# cc2652r.net
KiCad netlist of a schematic drawn in EAGLE
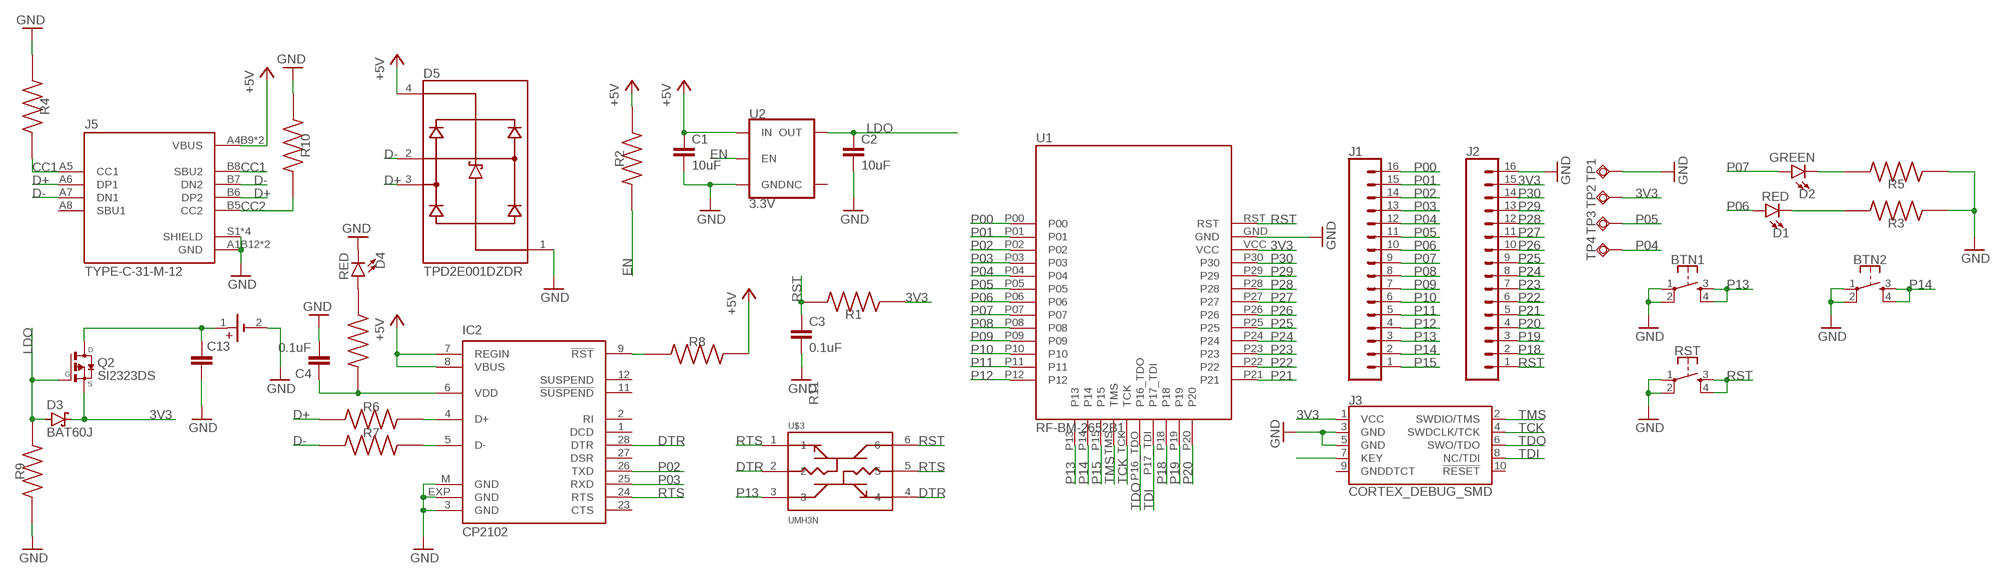
[diagram p0: schematic, sheet 1]

(export (version "E")
  (design (tool "Eeschema 10.0.6"))
  (components
    (comp (ref "BT2")
      (value "79527141")
      (footprint "eagle-import:79527141")
      (fields
        (field (name "DIGIKEY_PART_NO") "732-12325-2-ND")
        (field (name "MANUFACTURER") "Wurth Electronics Inc.")
        (field (name "CREATED_BY") "PCBLayout.com")
      )
      (libsource (lib "eagle-import") (part "79527141"))
    )
    (comp (ref "BTN1")
      (value "MOMENTARY-SWITCH-SPST-2-SMD-4.6X2.8MM")
      (footprint "eagle-import:TACTILE_SWITCH_SMD_4.6X2.8MM")
      (libsource (lib "eagle-import") (part "MOMENTARY-SWITCH-SPST-2-SMD-4.6X2.8MM"))
    )
    (comp (ref "BTN2")
      (value "MOMENTARY-SWITCH-SPST-2-SMD-4.6X2.8MM")
      (footprint "eagle-import:TACTILE_SWITCH_SMD_4.6X2.8MM")
      (libsource (lib "eagle-import") (part "MOMENTARY-SWITCH-SPST-2-SMD-4.6X2.8MM"))
    )
    (comp (ref "C1")
      (value "10uF")
      (footprint "eagle-import:0603")
      (libsource (lib "eagle-import") (part "10UF-0603-6.3V-20%"))
    )
    (comp (ref "C2")
      (value "10uF")
      (footprint "eagle-import:0603")
      (libsource (lib "eagle-import") (part "10UF-0603-6.3V-20%"))
    )
    (comp (ref "C3")
      (value "0.1uF")
      (footprint "eagle-import:0603")
      (libsource (lib "eagle-import") (part "0.1UF-0603-25V-(+80/-20%)"))
    )
    (comp (ref "C4")
      (value "0.1uF")
      (footprint "eagle-import:0603")
      (libsource (lib "eagle-import") (part "0.1UF-0603-25V-(+80/-20%)"))
    )
    (comp (ref "C13")
      (value "C_TANTALUM-2917(7343-METRIC)")
      (footprint "eagle-import:CAPM7343X310")
      (libsource (lib "eagle-import") (part "CTANTALUM-2917(7343-METRIC)_"))
    )
    (comp (ref "D1")
      (value "RED")
      (footprint "eagle-import:LED-0603")
      (libsource (lib "eagle-import") (part "LED-RED0603"))
    )
    (comp (ref "D2")
      (value "GREEN")
      (footprint "eagle-import:LED-0603")
      (libsource (lib "eagle-import") (part "LED-GREEN0603"))
    )
    (comp (ref "D3")
      (value "BAT60J")
      (footprint "eagle-import:SOD323_ST")
      (libsource (lib "eagle-import") (part "BAT60J"))
    )
    (comp (ref "D4")
      (value "RED")
      (footprint "eagle-import:LED-0603")
      (libsource (lib "eagle-import") (part "LED-RED0603"))
    )
    (comp (ref "D5")
      (value "TPD2E001DZDR")
      (footprint "eagle-import:SOT192P237X122-4N")
      (fields (field (name "MF") "Texas Instruments"))
      (libsource (lib "eagle-import") (part "TPD2E001DZDR"))
    )
    (comp (ref "IC2")
      (value "CP2102")
      (footprint "eagle-import:MLP28")
      (fields (field (name "MF") "FARNELL") (field (name "MPN") "CP2102-GM"))
      (libsource (lib "eagle-import") (part "CP2102"))
    )
    (comp (ref "J1")
      (value "CONN_161X16_NO_SILK")
      (footprint "eagle-import:1X16_NO_SILK")
      (libsource (lib "eagle-import") (part "CONN_161X16_NO_SILK"))
    )
    (comp (ref "J2")
      (value "CONN_161X16_NO_SILK")
      (footprint "eagle-import:1X16_NO_SILK")
      (libsource (lib "eagle-import") (part "CONN_161X16_NO_SILK"))
    )
    (comp (ref "J3")
      (value "CORTEX_DEBUG_SMD")
      (footprint "eagle-import:SAMTECH_FTSH-105-01")
      (libsource (lib "eagle-import") (part "CORTEX_DEBUG_SMD"))
    )
    (comp (ref "J5")
      (value "TYPE-C-31-M-12")
      (footprint "eagle-import:HRO_TYPE-C-31-M-12")
      (fields (field (name "MF") "HRO Electronics Co., Ltd."))
      (libsource (lib "eagle-import") (part "TYPE-C-31-M-12"))
    )
    (comp (ref "Q2")
      (value "SI2323DS")
      (footprint "eagle-import:SOT23")
      (fields (field (name "MF") "Vishay Siliconix"))
      (libsource (lib "eagle-import") (part "SI2323DS"))
    )
    (comp (ref "R1")
      (value "RC0402FR-073M6L")
      (footprint "eagle-import:RESC1005X40N")
      (fields (field (name "MF") "Yageo"))
      (libsource (lib "eagle-import") (part "RC0402FR-073M6L"))
    )
    (comp (ref "R2")
      (value "RC0402FR-073M6L")
      (footprint "eagle-import:RESC1005X40N")
      (fields (field (name "MF") "Yageo"))
      (libsource (lib "eagle-import") (part "RC0402FR-073M6L"))
    )
    (comp (ref "R3")
      (value "RC0402FR-073M6L")
      (footprint "eagle-import:RESC1005X40N")
      (fields (field (name "MF") "Yageo"))
      (libsource (lib "eagle-import") (part "RC0402FR-073M6L"))
    )
    (comp (ref "R4")
      (value "RC0402FR-073M6L")
      (footprint "eagle-import:RESC1005X40N")
      (fields (field (name "MF") "Yageo"))
      (libsource (lib "eagle-import") (part "RC0402FR-073M6L"))
    )
    (comp (ref "R5")
      (value "RC0402FR-073M6L")
      (footprint "eagle-import:RESC1005X40N")
      (fields (field (name "MF") "Yageo"))
      (libsource (lib "eagle-import") (part "RC0402FR-073M6L"))
    )
    (comp (ref "R6")
      (value "RC0402FR-073M6L")
      (footprint "eagle-import:RESC1005X40N")
      (fields (field (name "MF") "Yageo"))
      (libsource (lib "eagle-import") (part "RC0402FR-073M6L"))
    )
    (comp (ref "R7")
      (value "RC0402FR-073M6L")
      (footprint "eagle-import:RESC1005X40N")
      (fields (field (name "MF") "Yageo"))
      (libsource (lib "eagle-import") (part "RC0402FR-073M6L"))
    )
    (comp (ref "R8")
      (value "RC0402FR-073M6L")
      (footprint "eagle-import:RESC1005X40N")
      (fields (field (name "MF") "Yageo"))
      (libsource (lib "eagle-import") (part "RC0402FR-073M6L"))
    )
    (comp (ref "R9")
      (value "RC0402FR-073M6L")
      (footprint "eagle-import:RESC1005X40N")
      (fields (field (name "MF") "Yageo"))
      (libsource (lib "eagle-import") (part "RC0402FR-073M6L"))
    )
    (comp (ref "R10")
      (value "RC0402FR-073M6L")
      (footprint "eagle-import:RESC1005X40N")
      (fields (field (name "MF") "Yageo"))
      (libsource (lib "eagle-import") (part "RC0402FR-073M6L"))
    )
    (comp (ref "R11")
      (value "RC0402FR-073M6L")
      (footprint "eagle-import:RESC1005X40N")
      (fields (field (name "MF") "Yageo"))
      (libsource (lib "eagle-import") (part "RC0402FR-073M6L"))
    )
    (comp (ref "RST")
      (value "MOMENTARY-SWITCH-SPST-2-SMD-4.6X2.8MM")
      (footprint "eagle-import:TACTILE_SWITCH_SMD_4.6X2.8MM")
      (libsource (lib "eagle-import") (part "MOMENTARY-SWITCH-SPST-2-SMD-4.6X2.8MM"))
    )
    (comp (ref "TP1")
      (value "TPSQTP14R")
      (footprint "eagle-import:TP14R")
      (libsource (lib "eagle-import") (part "TPSQTP14R"))
    )
    (comp (ref "TP2")
      (value "TPSQTP14R")
      (footprint "eagle-import:TP14R")
      (libsource (lib "eagle-import") (part "TPSQTP14R"))
    )
    (comp (ref "TP3")
      (value "TPSQTP14R")
      (footprint "eagle-import:TP14R")
      (libsource (lib "eagle-import") (part "TPSQTP14R"))
    )
    (comp (ref "TP4")
      (value "TPSQTP14R")
      (footprint "eagle-import:TP14R")
      (libsource (lib "eagle-import") (part "TPSQTP14R"))
    )
    (comp (ref "U$3")
      (value "UMH3N")
      (footprint "eagle-import:SOP65P210X100-6N")
      (fields (field (name "MF") "Rohm"))
      (libsource (lib "eagle-import") (part "UMH3N"))
    )
    (comp (ref "U1")
      (value "RF-BM-2652B1")
      (footprint "eagle-import:RF-BM-2652B1")
      (libsource (lib "eagle-import") (part "RF-BM-2652B1"))
    )
    (comp (ref "U2")
      (value "3.3V")
      (footprint "eagle-import:SOT23-5")
      (libsource (lib "eagle-import") (part "V_REG_AP2112K-3.3V"))
    )
  )
  (nets
    (net (code "1") (name "+5V") (class "Default")
      (node (ref "C1") (pin "1") (pinfunction "1_1") (pintype "passive"))
      (node (ref "D5") (pin "4") (pinfunction "VCC_4") (pintype "power_in"))
      (node (ref "IC2") (pin "7") (pinfunction "REGIN_7") (pintype "passive"))
      (node (ref "IC2") (pin "8") (pinfunction "VBUS_8") (pintype "input"))
      (node (ref "J5") (pin "A4B9") (pinfunction "VBUS_A4B9") (pintype "power_in"))
      (node (ref "J5") (pin "B4A9") (pinfunction "VBUS_B4A9") (pintype "power_in"))
      (node (ref "R2") (pin "2") (pinfunction "2_2") (pintype "passive"))
      (node (ref "R8") (pin "2") (pinfunction "2_2") (pintype "passive"))
      (node (ref "U2") (pin "1") (pinfunction "IN_1") (pintype "input"))
    )
    (net (code "2") (name "/3V3") (class "Default")
      (node (ref "D3") (pin "C") (pinfunction "C_C") (pintype "passive"))
      (node (ref "J2") (pin "15") (pinfunction "15_15") (pintype "passive"))
      (node (ref "J3") (pin "1") (pinfunction "VCC_1") (pintype "bidirectional"))
      (node (ref "Q2") (pin "2") (pinfunction "S_2") (pintype "passive"))
      (node (ref "R1") (pin "1") (pinfunction "1_1") (pintype "passive"))
      (node (ref "TP2") (pin "TP") (pinfunction "TP_TP") (pintype "input"))
      (node (ref "U1") (pin "VCC") (pinfunction "VCC_VCC") (pintype "bidirectional"))
    )
    (net (code "3") (name "/CC1") (class "Default")
      (node (ref "J5") (pin "A5") (pinfunction "CC1_A5") (pintype "bidirectional"))
      (node (ref "J5") (pin "B8") (pinfunction "SBU2_B8") (pintype "bidirectional"))
      (node (ref "R4") (pin "2") (pinfunction "2_2") (pintype "passive"))
    )
    (net (code "4") (name "/CC2") (class "Default")
      (node (ref "J5") (pin "B5") (pinfunction "CC2_B5") (pintype "bidirectional"))
      (node (ref "R10") (pin "2") (pinfunction "2_2") (pintype "passive"))
    )
    (net (code "5") (name "/D+") (class "Default")
      (node (ref "D5") (pin "3") (pinfunction "IO2_3") (pintype "bidirectional"))
      (node (ref "J5") (pin "A6") (pinfunction "DP1_A6") (pintype "bidirectional"))
      (node (ref "J5") (pin "B6") (pinfunction "DP2_B6") (pintype "bidirectional"))
      (node (ref "R6") (pin "1") (pinfunction "1_1") (pintype "passive"))
    )
    (net (code "6") (name "/D-") (class "Default")
      (node (ref "D5") (pin "2") (pinfunction "IO1_2") (pintype "bidirectional"))
      (node (ref "J5") (pin "A7") (pinfunction "DN1_A7") (pintype "bidirectional"))
      (node (ref "J5") (pin "B7") (pinfunction "DN2_B7") (pintype "bidirectional"))
      (node (ref "R7") (pin "1") (pinfunction "1_1") (pintype "passive"))
    )
    (net (code "7") (name "/DTR") (class "Default")
      (node (ref "IC2") (pin "28") (pinfunction "DTR_28") (pintype "output"))
      (node (ref "U$3") (pin "2") (pinfunction "2_2") (pintype "bidirectional"))
      (node (ref "U$3") (pin "4") (pinfunction "4_4") (pintype "bidirectional"))
    )
    (net (code "8") (name "/EN") (class "Default")
      (node (ref "R2") (pin "1") (pinfunction "1_1") (pintype "passive"))
      (node (ref "U2") (pin "3") (pinfunction "EN_3") (pintype "input"))
    )
    (net (code "9") (name "/LDO") (class "Default")
      (node (ref "C2") (pin "1") (pinfunction "1_1") (pintype "passive"))
      (node (ref "D3") (pin "A") (pinfunction "A_A") (pintype "passive"))
      (node (ref "Q2") (pin "1") (pinfunction "G_1") (pintype "passive"))
      (node (ref "R9") (pin "2") (pinfunction "2_2") (pintype "passive"))
      (node (ref "U2") (pin "5") (pinfunction "OUT_5") (pintype "passive"))
    )
    (net (code "10") (name "/P00") (class "Default")
      (node (ref "J1") (pin "16") (pinfunction "16_16") (pintype "passive"))
      (node (ref "U1") (pin "P00") (pinfunction "P00_P00") (pintype "bidirectional"))
    )
    (net (code "11") (name "/P01") (class "Default")
      (node (ref "J1") (pin "15") (pinfunction "15_15") (pintype "passive"))
      (node (ref "U1") (pin "P01") (pinfunction "P01_P01") (pintype "bidirectional"))
    )
    (net (code "12") (name "/P02") (class "Default")
      (node (ref "IC2") (pin "26") (pinfunction "TXD_26") (pintype "output"))
      (node (ref "J1") (pin "14") (pinfunction "14_14") (pintype "passive"))
      (node (ref "U1") (pin "P02") (pinfunction "P02_P02") (pintype "bidirectional"))
    )
    (net (code "13") (name "/P03") (class "Default")
      (node (ref "IC2") (pin "25") (pinfunction "RXD_25") (pintype "input"))
      (node (ref "J1") (pin "13") (pinfunction "13_13") (pintype "passive"))
      (node (ref "U1") (pin "P03") (pinfunction "P03_P03") (pintype "bidirectional"))
    )
    (net (code "14") (name "/P04") (class "Default")
      (node (ref "J1") (pin "12") (pinfunction "12_12") (pintype "passive"))
      (node (ref "TP4") (pin "TP") (pinfunction "TP_TP") (pintype "input"))
      (node (ref "U1") (pin "P04") (pinfunction "P04_P04") (pintype "bidirectional"))
    )
    (net (code "15") (name "/P05") (class "Default")
      (node (ref "J1") (pin "11") (pinfunction "11_11") (pintype "passive"))
      (node (ref "TP3") (pin "TP") (pinfunction "TP_TP") (pintype "input"))
      (node (ref "U1") (pin "P05") (pinfunction "P05_P05") (pintype "bidirectional"))
    )
    (net (code "16") (name "/P06") (class "Default")
      (node (ref "D1") (pin "A") (pinfunction "A_A") (pintype "passive"))
      (node (ref "J1") (pin "10") (pinfunction "10_10") (pintype "passive"))
      (node (ref "U1") (pin "P06") (pinfunction "P06_P06") (pintype "bidirectional"))
    )
    (net (code "17") (name "/P07") (class "Default")
      (node (ref "D2") (pin "A") (pinfunction "A_A") (pintype "passive"))
      (node (ref "J1") (pin "9") (pinfunction "9_9") (pintype "passive"))
      (node (ref "U1") (pin "P07") (pinfunction "P07_P07") (pintype "bidirectional"))
    )
    (net (code "18") (name "/P08") (class "Default")
      (node (ref "J1") (pin "8") (pinfunction "8_8") (pintype "passive"))
      (node (ref "U1") (pin "P08") (pinfunction "P08_P08") (pintype "bidirectional"))
    )
    (net (code "19") (name "/P09") (class "Default")
      (node (ref "J1") (pin "7") (pinfunction "7_7") (pintype "passive"))
      (node (ref "U1") (pin "P09") (pinfunction "P09_P09") (pintype "bidirectional"))
    )
    (net (code "20") (name "/P10") (class "Default")
      (node (ref "J1") (pin "6") (pinfunction "6_6") (pintype "passive"))
      (node (ref "U1") (pin "P10") (pinfunction "P10_P10") (pintype "bidirectional"))
    )
    (net (code "21") (name "/P11") (class "Default")
      (node (ref "J1") (pin "5") (pinfunction "5_5") (pintype "passive"))
      (node (ref "U1") (pin "P11") (pinfunction "P11_P11") (pintype "bidirectional"))
    )
    (net (code "22") (name "/P12") (class "Default")
      (node (ref "J1") (pin "4") (pinfunction "4_4") (pintype "passive"))
      (node (ref "U1") (pin "P12") (pinfunction "P12_P12") (pintype "bidirectional"))
    )
    (net (code "23") (name "/P13") (class "Default")
      (node (ref "BTN1") (pin "3") (pinfunction "3_3") (pintype "passive"))
      (node (ref "BTN1") (pin "4") (pinfunction "4_4") (pintype "passive"))
      (node (ref "J1") (pin "3") (pinfunction "3_3") (pintype "passive"))
      (node (ref "U$3") (pin "3") (pinfunction "3_3") (pintype "bidirectional"))
      (node (ref "U1") (pin "P13") (pinfunction "P13_P13") (pintype "bidirectional"))
    )
    (net (code "24") (name "/P14") (class "Default")
      (node (ref "BTN2") (pin "3") (pinfunction "3_3") (pintype "passive"))
      (node (ref "BTN2") (pin "4") (pinfunction "4_4") (pintype "passive"))
      (node (ref "J1") (pin "2") (pinfunction "2_2") (pintype "passive"))
      (node (ref "U1") (pin "P14") (pinfunction "P14_P14") (pintype "bidirectional"))
    )
    (net (code "25") (name "/P15") (class "Default")
      (node (ref "J1") (pin "1") (pinfunction "1_1") (pintype "passive"))
      (node (ref "U1") (pin "P15") (pinfunction "P15_P15") (pintype "bidirectional"))
    )
    (net (code "26") (name "/P18") (class "Default")
      (node (ref "J2") (pin "2") (pinfunction "2_2") (pintype "passive"))
      (node (ref "U1") (pin "P18") (pinfunction "P18_P18") (pintype "bidirectional"))
    )
    (net (code "27") (name "/P19") (class "Default")
      (node (ref "J2") (pin "3") (pinfunction "3_3") (pintype "passive"))
      (node (ref "U1") (pin "P19") (pinfunction "P19_P19") (pintype "bidirectional"))
    )
    (net (code "28") (name "/P20") (class "Default")
      (node (ref "J2") (pin "4") (pinfunction "4_4") (pintype "passive"))
      (node (ref "U1") (pin "P20") (pinfunction "P20_P20") (pintype "bidirectional"))
    )
    (net (code "29") (name "/P21") (class "Default")
      (node (ref "J2") (pin "5") (pinfunction "5_5") (pintype "passive"))
      (node (ref "U1") (pin "P21") (pinfunction "P21_P21") (pintype "bidirectional"))
    )
    (net (code "30") (name "/P22") (class "Default")
      (node (ref "J2") (pin "6") (pinfunction "6_6") (pintype "passive"))
      (node (ref "U1") (pin "P22") (pinfunction "P22_P22") (pintype "bidirectional"))
    )
    (net (code "31") (name "/P23") (class "Default")
      (node (ref "J2") (pin "7") (pinfunction "7_7") (pintype "passive"))
      (node (ref "U1") (pin "P23") (pinfunction "P23_P23") (pintype "bidirectional"))
    )
    (net (code "32") (name "/P24") (class "Default")
      (node (ref "J2") (pin "8") (pinfunction "8_8") (pintype "passive"))
      (node (ref "U1") (pin "P24") (pinfunction "P24_P24") (pintype "bidirectional"))
    )
    (net (code "33") (name "/P25") (class "Default")
      (node (ref "J2") (pin "9") (pinfunction "9_9") (pintype "passive"))
      (node (ref "U1") (pin "P25") (pinfunction "P25_P25") (pintype "bidirectional"))
    )
    (net (code "34") (name "/P26") (class "Default")
      (node (ref "J2") (pin "10") (pinfunction "10_10") (pintype "passive"))
      (node (ref "U1") (pin "P26") (pinfunction "P26_P26") (pintype "bidirectional"))
    )
    (net (code "35") (name "/P27") (class "Default")
      (node (ref "J2") (pin "11") (pinfunction "11_11") (pintype "passive"))
      (node (ref "U1") (pin "P27") (pinfunction "P27_P27") (pintype "bidirectional"))
    )
    (net (code "36") (name "/P28") (class "Default")
      (node (ref "J2") (pin "12") (pinfunction "12_12") (pintype "passive"))
      (node (ref "U1") (pin "P28") (pinfunction "P28_P28") (pintype "bidirectional"))
    )
    (net (code "37") (name "/P29") (class "Default")
      (node (ref "J2") (pin "13") (pinfunction "13_13") (pintype "passive"))
      (node (ref "U1") (pin "P29") (pinfunction "P29_P29") (pintype "bidirectional"))
    )
    (net (code "38") (name "/P30") (class "Default")
      (node (ref "J2") (pin "14") (pinfunction "14_14") (pintype "passive"))
      (node (ref "U1") (pin "P30") (pinfunction "P30_P30") (pintype "bidirectional"))
    )
    (net (code "39") (name "/RST") (class "Default")
      (node (ref "C3") (pin "1") (pinfunction "1_1") (pintype "passive"))
      (node (ref "J2") (pin "1") (pinfunction "1_1") (pintype "passive"))
      (node (ref "R1") (pin "2") (pinfunction "2_2") (pintype "passive"))
      (node (ref "RST") (pin "3") (pinfunction "3_3") (pintype "passive"))
      (node (ref "RST") (pin "4") (pinfunction "4_4") (pintype "passive"))
      (node (ref "U$3") (pin "6") (pinfunction "6_6") (pintype "bidirectional"))
      (node (ref "U1") (pin "RST") (pinfunction "RST_RST") (pintype "bidirectional"))
    )
    (net (code "40") (name "/RTS") (class "Default")
      (node (ref "IC2") (pin "24") (pinfunction "RTS_24") (pintype "output"))
      (node (ref "U$3") (pin "1") (pinfunction "1_1") (pintype "bidirectional"))
      (node (ref "U$3") (pin "5") (pinfunction "5_5") (pintype "bidirectional"))
    )
    (net (code "41") (name "/TCK") (class "Default")
      (node (ref "J3") (pin "4") (pinfunction "SWDCLK/TCK_4") (pintype "bidirectional"))
      (node (ref "U1") (pin "TCK") (pinfunction "TCK_TCK") (pintype "bidirectional"))
    )
    (net (code "42") (name "/TDI") (class "Default")
      (node (ref "J3") (pin "8") (pinfunction "NC/TDI_8") (pintype "bidirectional"))
      (node (ref "U1") (pin "P17_TDI") (pinfunction "P17_TDI_P17_TDI") (pintype "bidirectional"))
    )
    (net (code "43") (name "/TDO") (class "Default")
      (node (ref "J3") (pin "6") (pinfunction "SWO/TDO_6") (pintype "bidirectional"))
      (node (ref "U1") (pin "P16_TDO") (pinfunction "P16_TDO_P16_TDO") (pintype "bidirectional"))
    )
    (net (code "44") (name "/TMS") (class "Default")
      (node (ref "J3") (pin "2") (pinfunction "SWDIO/TMS_2") (pintype "bidirectional"))
      (node (ref "U1") (pin "TMS") (pinfunction "TMS_TMS") (pintype "bidirectional"))
    )
    (net (code "45") (name "GND") (class "Default")
      (node (ref "BT2") (pin "2") (pinfunction "-_2") (pintype "passive"))
      (node (ref "BTN1") (pin "1") (pinfunction "1_1") (pintype "passive"))
      (node (ref "BTN1") (pin "2") (pinfunction "2_2") (pintype "passive"))
      (node (ref "BTN2") (pin "1") (pinfunction "1_1") (pintype "passive"))
      (node (ref "BTN2") (pin "2") (pinfunction "2_2") (pintype "passive"))
      (node (ref "C1") (pin "2") (pinfunction "2_2") (pintype "passive"))
      (node (ref "C13") (pin "2") (pinfunction "2_2") (pintype "passive"))
      (node (ref "C2") (pin "2") (pinfunction "2_2") (pintype "passive"))
      (node (ref "C3") (pin "2") (pinfunction "2_2") (pintype "passive"))
      (node (ref "C4") (pin "2") (pinfunction "2_2") (pintype "passive"))
      (node (ref "D4") (pin "C") (pinfunction "C_C") (pintype "passive"))
      (node (ref "D5") (pin "1") (pinfunction "GND_1") (pintype "power_in"))
      (node (ref "IC2") (pin "3") (pinfunction "GND_3") (pintype "power_in"))
      (node (ref "IC2") (pin "EXP") (pinfunction "GND_EXP") (pintype "power_in"))
      (node (ref "IC2") (pin "M") (pinfunction "GND_M") (pintype "power_in"))
      (node (ref "J2") (pin "16") (pinfunction "16_16") (pintype "passive"))
      (node (ref "J3") (pin "3") (pinfunction "GND_3") (pintype "bidirectional"))
      (node (ref "J3") (pin "5") (pinfunction "GND_5") (pintype "bidirectional"))
      (node (ref "J5") (pin "A1B12") (pinfunction "GND_A1B12") (pintype "power_in"))
      (node (ref "J5") (pin "B1A12") (pinfunction "GND_B1A12") (pintype "power_in"))
      (node (ref "J5") (pin "S1") (pinfunction "SHIELD_S1") (pintype "passive"))
      (node (ref "J5") (pin "S2") (pinfunction "SHIELD_S2") (pintype "passive"))
      (node (ref "J5") (pin "S3") (pinfunction "SHIELD_S3") (pintype "passive"))
      (node (ref "J5") (pin "S4") (pinfunction "SHIELD_S4") (pintype "passive"))
      (node (ref "R10") (pin "1") (pinfunction "1_1") (pintype "passive"))
      (node (ref "R3") (pin "1") (pinfunction "1_1") (pintype "passive"))
      (node (ref "R4") (pin "1") (pinfunction "1_1") (pintype "passive"))
      (node (ref "R5") (pin "1") (pinfunction "1_1") (pintype "passive"))
      (node (ref "R9") (pin "1") (pinfunction "1_1") (pintype "passive"))
      (node (ref "RST") (pin "1") (pinfunction "1_1") (pintype "passive"))
      (node (ref "RST") (pin "2") (pinfunction "2_2") (pintype "passive"))
      (node (ref "TP1") (pin "TP") (pinfunction "TP_TP") (pintype "input"))
      (node (ref "U1") (pin "GND") (pinfunction "GND_GND") (pintype "bidirectional"))
      (node (ref "U2") (pin "2") (pinfunction "GND_2") (pintype "input"))
    )
    (net (code "46") (name "Net-(BT2-+)") (class "Default")
      (node (ref "BT2") (pin "1") (pinfunction "+_1") (pintype "passive"))
      (node (ref "C13") (pin "1") (pinfunction "1_1") (pintype "passive"))
      (node (ref "Q2") (pin "3") (pinfunction "D_3") (pintype "passive"))
    )
    (net (code "47") (name "Net-(D1-PadC)") (class "Default")
      (node (ref "D1") (pin "C") (pinfunction "C_C") (pintype "passive"))
      (node (ref "R3") (pin "2") (pinfunction "2_2") (pintype "passive"))
    )
    (net (code "48") (name "Net-(D2-PadC)") (class "Default")
      (node (ref "D2") (pin "C") (pinfunction "C_C") (pintype "passive"))
      (node (ref "R5") (pin "2") (pinfunction "2_2") (pintype "passive"))
    )
    (net (code "49") (name "Net-(D4-PadA)") (class "Default")
      (node (ref "D4") (pin "A") (pinfunction "A_A") (pintype "passive"))
      (node (ref "R11") (pin "1") (pinfunction "1_1") (pintype "passive"))
    )
    (net (code "50") (name "Net-(IC2-D+)") (class "Default")
      (node (ref "IC2") (pin "4") (pinfunction "D+_4") (pintype "bidirectional"))
      (node (ref "R6") (pin "2") (pinfunction "2_2") (pintype "passive"))
    )
    (net (code "51") (name "Net-(IC2-D-)") (class "Default")
      (node (ref "IC2") (pin "5") (pinfunction "D-_5") (pintype "bidirectional"))
      (node (ref "R7") (pin "2") (pinfunction "2_2") (pintype "passive"))
    )
    (net (code "52") (name "Net-(IC2-VDD)") (class "Default")
      (node (ref "C4") (pin "1") (pinfunction "1_1") (pintype "passive"))
      (node (ref "IC2") (pin "6") (pinfunction "VDD_6") (pintype "power_in"))
      (node (ref "R11") (pin "2") (pinfunction "2_2") (pintype "passive"))
    )
    (net (code "53") (name "Net-(IC2-~{RST})") (class "Default")
      (node (ref "IC2") (pin "9") (pinfunction "~{RST}_9") (pintype "bidirectional"))
      (node (ref "R8") (pin "1") (pinfunction "1_1") (pintype "passive"))
    )
    (net (code "54") (name "unconnected-(IC2-CTS-Pad23)") (class "Default")
      (node (ref "IC2") (pin "23") (pinfunction "CTS_23") (pintype "input"))
    )
    (net (code "55") (name "unconnected-(IC2-DCD-Pad1)") (class "Default")
      (node (ref "IC2") (pin "1") (pinfunction "DCD_1") (pintype "input"))
    )
    (net (code "56") (name "unconnected-(IC2-DSR-Pad27)") (class "Default")
      (node (ref "IC2") (pin "27") (pinfunction "DSR_27") (pintype "input"))
    )
    (net (code "57") (name "unconnected-(IC2-RI-Pad2)") (class "Default")
      (node (ref "IC2") (pin "2") (pinfunction "RI_2") (pintype "input"))
    )
    (net (code "58") (name "unconnected-(IC2-SUSPEND-Pad12)") (class "Default")
      (node (ref "IC2") (pin "12") (pinfunction "SUSPEND_12") (pintype "output"))
    )
    (net (code "59") (name "unconnected-(IC2-~{SUSPEND}-Pad11)") (class "Default")
      (node (ref "IC2") (pin "11") (pinfunction "~{SUSPEND}_11") (pintype "output"))
    )
    (net (code "60") (name "unconnected-(J3-GNDDTCT-Pad9)") (class "Default")
      (node (ref "J3") (pin "9") (pinfunction "GNDDTCT_9") (pintype "bidirectional"))
    )
    (net (code "61") (name "unconnected-(J3-KEY-Pad7)") (class "Default")
      (node (ref "J3") (pin "7") (pinfunction "KEY_7") (pintype "bidirectional"))
    )
    (net (code "62") (name "unconnected-(J3-~{RESET}-Pad10)") (class "Default")
      (node (ref "J3") (pin "10") (pinfunction "~{RESET}_10") (pintype "bidirectional"))
    )
    (net (code "63") (name "unconnected-(J5-SBU1-PadA8)") (class "Default")
      (node (ref "J5") (pin "A8") (pinfunction "SBU1_A8") (pintype "bidirectional"))
    )
    (net (code "64") (name "unconnected-(U2-NC-Pad4)") (class "Default")
      (node (ref "U2") (pin "4") (pinfunction "NC_4") (pintype "no_connect"))
    )
  )
)
